# PAGE06_POWER_SWITCHES.net
KiCad netlist of a schematic drawn in Altium Designer
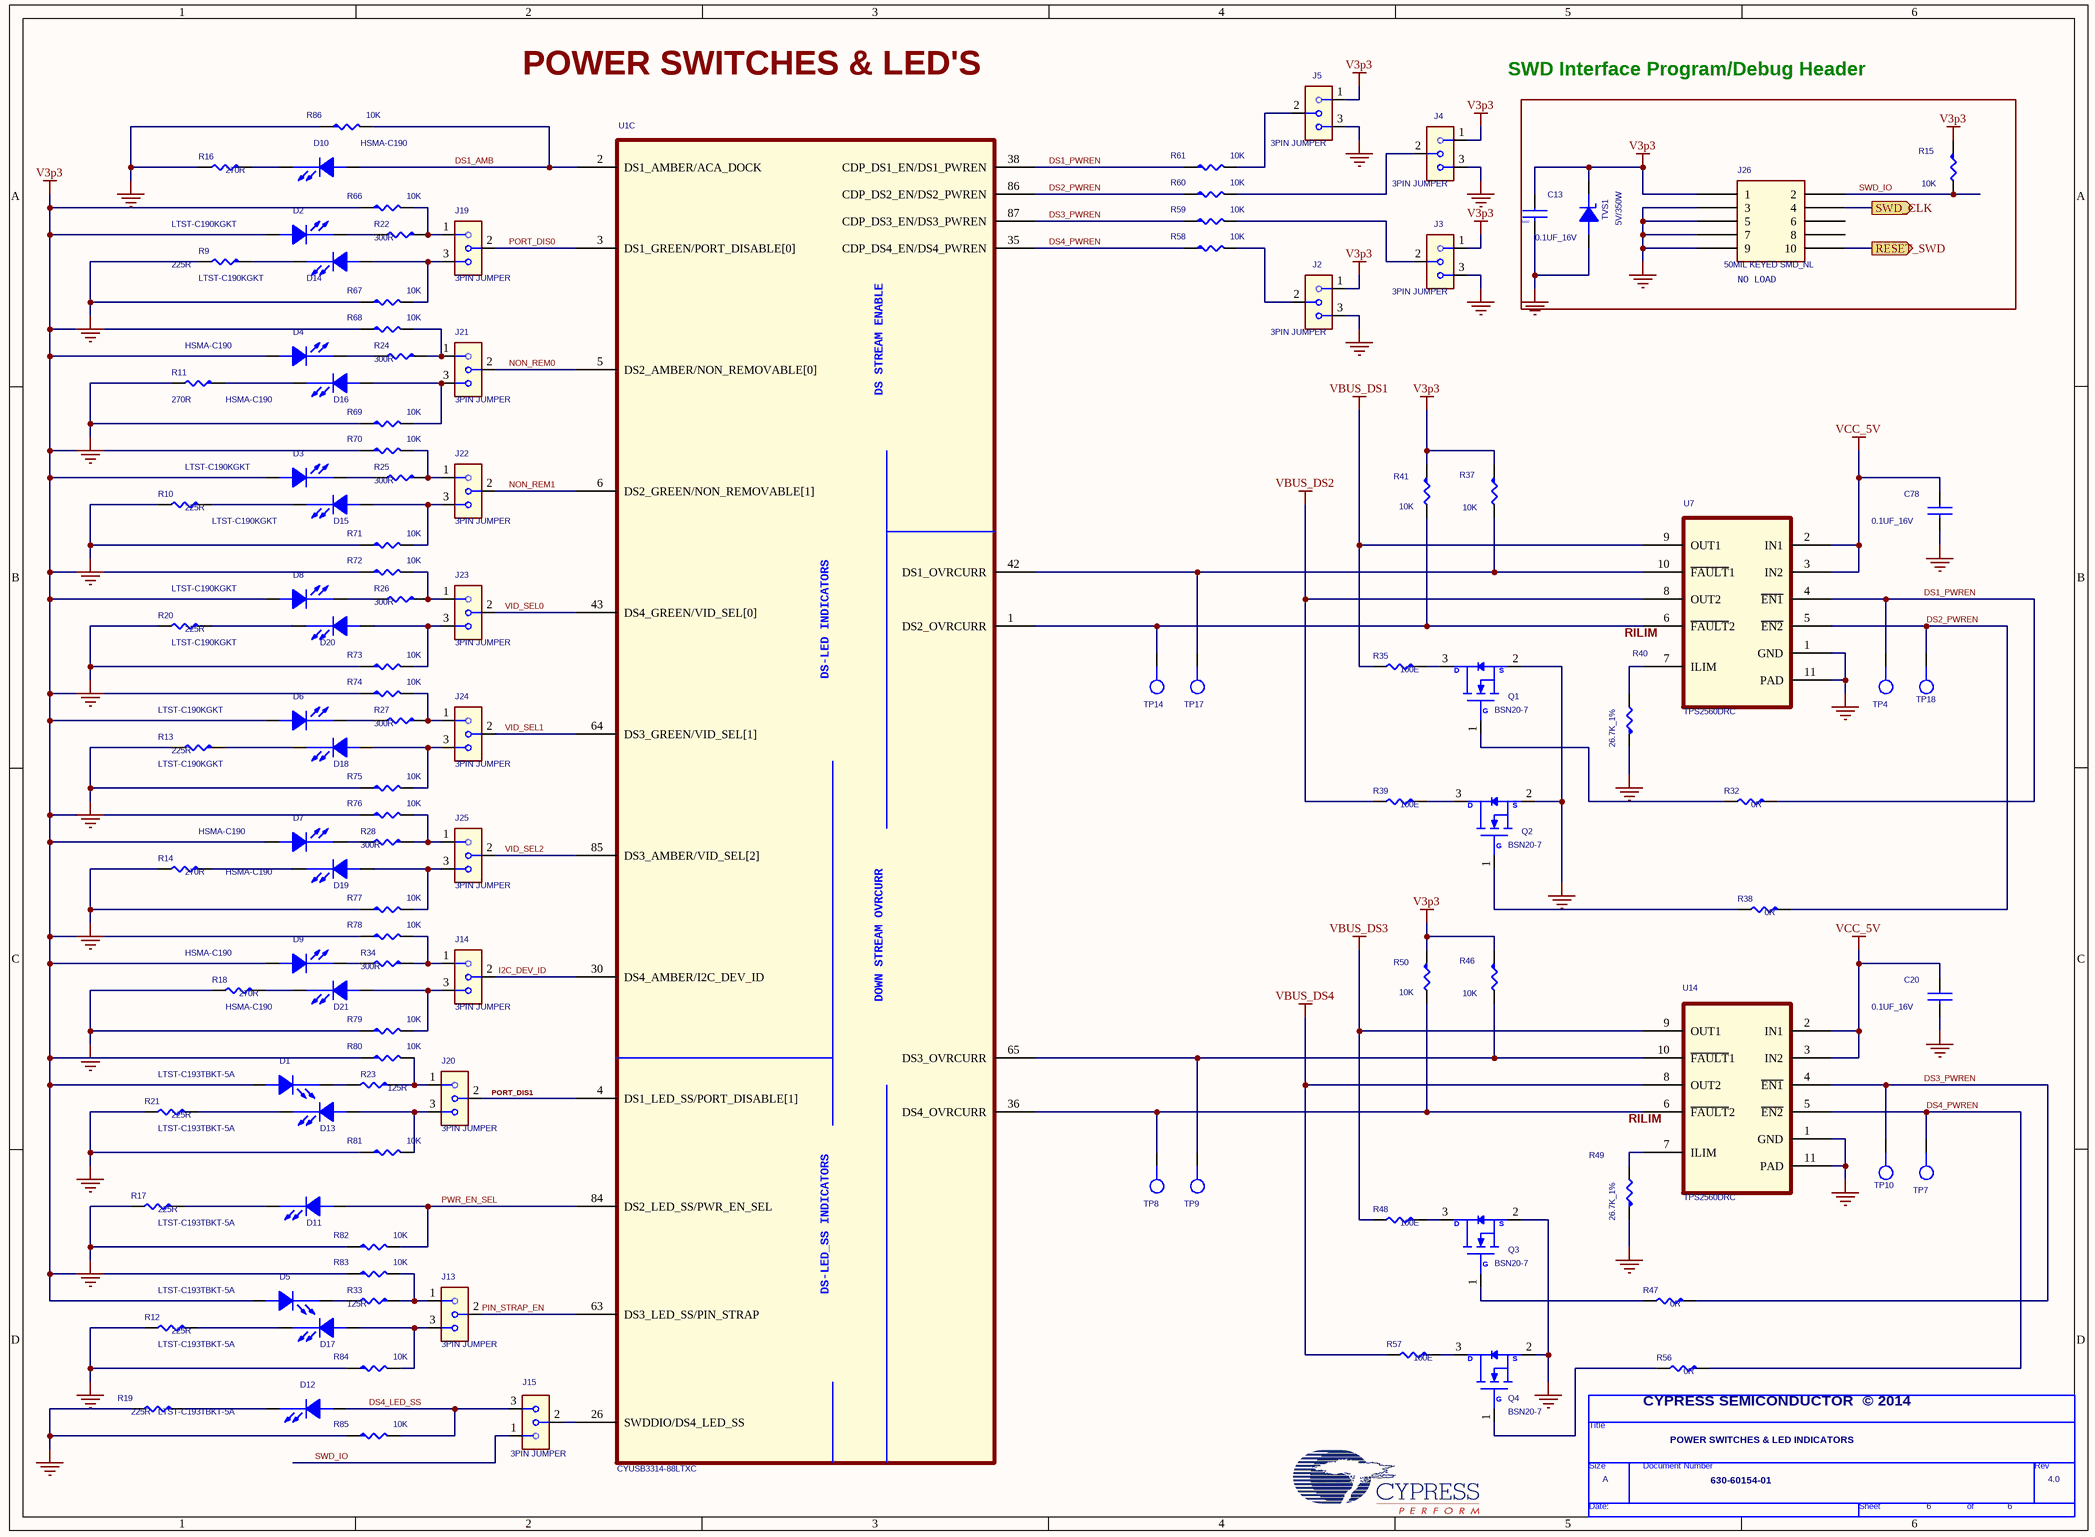
[diagram p0: PAGE06_POWER SWITCHES &.SchDoc]

(export (version "E")
  (design (tool "Eeschema 10.0.6"))
  (components
    (comp (ref "*")
      (value "TitleBlock0")
      (fields
        (field (name "PAGE COUNT") "6")
        (field (name "PAGE NUMBER") "6")
        (field (name "PAGE SIZE") "A")
        (field (name "TITLE") "POWER SWITCHES & LED INDICATORS")
        (field (name "REVCODE") "4.0")
        (field (name "DOC") "630-60154-01")
      )
      (libsource (lib "*") (part "TitleBlock0"))
    )
    (comp (ref "C13")
      (value "0.1UF_16V")
      (footprint "CAPC1005X55M")
      (description "CAP .1UF 16V CERAMIC Y5V 0402")
      (fields
        (field (name "CY_PART#") "730R-10010")
        (field (name "MANUFACTURER") "Panasonic - ECG")
        (field (name "CREATED BY") "SNF")
      )
      (libsource (lib "*") (part "0.1 uFd 0402"))
    )
    (comp (ref "C20")
      (value "0.1UF_16V")
      (footprint "CAPC1005X56M")
      (libsource (lib "*") (part "CAPACITOR NON-POL"))
    )
    (comp (ref "C78")
      (value "0.1UF_16V")
      (footprint "CAPC1005X56M")
      (libsource (lib "*") (part "CAPACITOR NON-POL"))
    )
    (comp (ref "D1") (value "LTST-C193TBKT-5A") (libsource (lib "*") (part "LED")))
    (comp (ref "D2") (value "LTST-C190KGKT") (libsource (lib "*") (part "LED")))
    (comp (ref "D3") (value "LTST-C190KGKT") (libsource (lib "*") (part "LED")))
    (comp (ref "D4") (value "HSMA-C190") (libsource (lib "*") (part "LED")))
    (comp (ref "D5") (value "LTST-C193TBKT-5A") (libsource (lib "*") (part "LED")))
    (comp (ref "D6") (value "LTST-C190KGKT") (libsource (lib "*") (part "LED")))
    (comp (ref "D7") (value "HSMA-C190") (libsource (lib "*") (part "LED")))
    (comp (ref "D8") (value "LTST-C190KGKT") (libsource (lib "*") (part "LED")))
    (comp (ref "D9") (value "HSMA-C190") (libsource (lib "*") (part "LED")))
    (comp (ref "D10") (value "HSMA-C190") (libsource (lib "*") (part "LED")))
    (comp (ref "D11") (value "LTST-C193TBKT-5A") (libsource (lib "*") (part "LED")))
    (comp (ref "D12") (value "LTST-C193TBKT-5A") (libsource (lib "*") (part "LED")))
    (comp (ref "D13") (value "LTST-C193TBKT-5A") (libsource (lib "*") (part "LED")))
    (comp (ref "D14") (value "LTST-C190KGKT") (libsource (lib "*") (part "LED")))
    (comp (ref "D15") (value "LTST-C190KGKT") (libsource (lib "*") (part "LED")))
    (comp (ref "D16") (value "HSMA-C190") (libsource (lib "*") (part "LED")))
    (comp (ref "D17") (value "LTST-C193TBKT-5A") (libsource (lib "*") (part "LED")))
    (comp (ref "D18") (value "LTST-C190KGKT") (libsource (lib "*") (part "LED")))
    (comp (ref "D19") (value "HSMA-C190") (libsource (lib "*") (part "LED")))
    (comp (ref "D20") (value "LTST-C190KGKT") (libsource (lib "*") (part "LED")))
    (comp (ref "D21") (value "HSMA-C190") (libsource (lib "*") (part "LED")))
    (comp (ref "J2")
      (value "3PIN JUMPER")
      (description "CONN HEADER VERT 3POS .100 TIN")
      (fields (field (name "MANUFACTURER") "Tyco Electronics") (field (name "PART NUMBER") "3-644456-3"))
      (libsource (lib "*") (part "3PIN JUM"))
    )
    (comp (ref "J3")
      (value "3PIN JUMPER")
      (description "CONN HEADER VERT 3POS .100 TIN")
      (fields (field (name "PART NUMBER") "3-644456-3") (field (name "MANUFACTURER") "Tyco Electronics"))
      (libsource (lib "*") (part "3PIN JUM"))
    )
    (comp (ref "J4")
      (value "3PIN JUMPER")
      (description "CONN HEADER VERT 3POS .100 TIN")
      (fields (field (name "MANUFACTURER") "Tyco Electronics") (field (name "PART NUMBER") "3-644456-3"))
      (libsource (lib "*") (part "3PIN JUM"))
    )
    (comp (ref "J5")
      (value "3PIN JUMPER")
      (description "CONN HEADER VERT 3POS .100 TIN")
      (fields (field (name "PART NUMBER") "3-644456-3") (field (name "MANUFACTURER") "Tyco Electronics"))
      (libsource (lib "*") (part "3PIN JUM"))
    )
    (comp (ref "J13")
      (value "3PIN JUMPER")
      (description "CONN HEADER VERT 3POS .100 TIN")
      (fields (field (name "PART NUMBER") "3-644456-3") (field (name "MANUFACTURER") "Tyco Electronics"))
      (libsource (lib "") (part "3PIN JUM_1"))
    )
    (comp (ref "J14")
      (value "3PIN JUMPER")
      (description "CONN HEADER VERT 3POS .100 TIN")
      (fields (field (name "MANUFACTURER") "Tyco Electronics") (field (name "PART NUMBER") "3-644456-3"))
      (libsource (lib "") (part "3PIN JUM_1"))
    )
    (comp (ref "J15")
      (value "3PIN JUMPER")
      (description "CONN HEADER VERT 3POS .100 TIN")
      (fields (field (name "PART NUMBER") "3-644456-3") (field (name "MANUFACTURER") "Tyco Electronics"))
      (libsource (lib "") (part "3PIN JUM_2"))
    )
    (comp (ref "J19")
      (value "3PIN JUMPER")
      (description "CONN HEADER VERT 3POS .100 TIN")
      (fields (field (name "PART NUMBER") "3-644456-3") (field (name "MANUFACTURER") "Tyco Electronics"))
      (libsource (lib "") (part "3PIN JUM_1"))
    )
    (comp (ref "J20")
      (value "3PIN JUMPER")
      (description "CONN HEADER VERT 3POS .100 TIN")
      (fields (field (name "PART NUMBER") "3-644456-3") (field (name "MANUFACTURER") "Tyco Electronics"))
      (libsource (lib "") (part "3PIN JUM_1"))
    )
    (comp (ref "J21")
      (value "3PIN JUMPER")
      (description "CONN HEADER VERT 3POS .100 TIN")
      (fields (field (name "PART NUMBER") "3-644456-3") (field (name "MANUFACTURER") "Tyco Electronics"))
      (libsource (lib "") (part "3PIN JUM_1"))
    )
    (comp (ref "J22")
      (value "3PIN JUMPER")
      (description "CONN HEADER VERT 3POS .100 TIN")
      (fields (field (name "PART NUMBER") "3-644456-3") (field (name "MANUFACTURER") "Tyco Electronics"))
      (libsource (lib "") (part "3PIN JUM_1"))
    )
    (comp (ref "J23")
      (value "3PIN JUMPER")
      (description "CONN HEADER VERT 3POS .100 TIN")
      (fields (field (name "MANUFACTURER") "Tyco Electronics") (field (name "PART NUMBER") "3-644456-3"))
      (libsource (lib "") (part "3PIN JUM_1"))
    )
    (comp (ref "J24")
      (value "3PIN JUMPER")
      (description "CONN HEADER VERT 3POS .100 TIN")
      (fields (field (name "PART NUMBER") "3-644456-3") (field (name "MANUFACTURER") "Tyco Electronics"))
      (libsource (lib "") (part "3PIN JUM_1"))
    )
    (comp (ref "J25")
      (value "3PIN JUMPER")
      (description "CONN HEADER VERT 3POS .100 TIN")
      (fields (field (name "MANUFACTURER") "Tyco Electronics") (field (name "PART NUMBER") "3-644456-3"))
      (libsource (lib "") (part "3PIN JUM_1"))
    )
    (comp (ref "J26")
      (value "50MIL KEYED SMD_NL")
      (footprint "SAMTEC_FTSH-105-01-L-DV-K")
      (description "CONN HEADER 10 PIN 50MIL KEYED SMD")
      (fields
        (field (name "PART NUMBER") "FTSH-105-01-L-DV-K")
        (field (name "MANUFACTURER") "Samtec")
        (field (name "LAST EDIT BY") "SNF")
      )
      (libsource (lib "*") (part "10 Pin Header 50mil Keyed SMD"))
    )
    (comp (ref "Q1")
      (value "BSN20-7")
      (description "MOSFET N-CH 50V 500MA SOT23")
      (fields (field (name "MANUFACTURER") "Diodes Inc"))
      (libsource (lib "*") (part "BSN20-7"))
    )
    (comp (ref "Q2")
      (value "BSN20-7")
      (description "MOSFET N-CH 50V 500MA SOT23")
      (fields (field (name "MANUFACTURER") "Diodes Inc"))
      (libsource (lib "*") (part "BSN20-7"))
    )
    (comp (ref "Q3")
      (value "BSN20-7")
      (description "MOSFET N-CH 50V 500MA SOT23")
      (fields (field (name "MANUFACTURER") "Diodes Inc"))
      (libsource (lib "*") (part "BSN20-7"))
    )
    (comp (ref "Q4")
      (value "BSN20-7")
      (description "MOSFET N-CH 50V 500MA SOT23")
      (fields (field (name "MANUFACTURER") "Diodes Inc"))
      (libsource (lib "*") (part "BSN20-7"))
    )
    (comp (ref "R9") (value "225R") (footprint "RESC1608X50M") (libsource (lib "*") (part "R_Dup1")))
    (comp (ref "R10") (value "225R") (footprint "RESC1608X50M") (libsource (lib "*") (part "R_Dup1")))
    (comp (ref "R11") (value "270R") (footprint "RESC1608X50M") (libsource (lib "*") (part "R_Dup1")))
    (comp (ref "R12") (value "225R") (footprint "RESC1608X50M") (libsource (lib "*") (part "R_Dup1")))
    (comp (ref "R13") (value "225R") (footprint "RESC1608X50M") (libsource (lib "*") (part "R_Dup1")))
    (comp (ref "R14") (value "270R") (footprint "RESC1608X50M") (libsource (lib "*") (part "R_Dup1")))
    (comp (ref "R15")
      (value "10K")
      (footprint "RESC1005X40M")
      (description "RES 10.0K OHM 1/10W 1% 0603 SMD")
      (fields (field (name "MANUFACTURER") "Panasonic - ECG") (field (name "PART NUMBER") "ERJ-3EKF1002V"))
      (libsource (lib "*") (part "R_Dup1"))
    )
    (comp (ref "R16") (value "270R") (footprint "RESC1608X50M") (libsource (lib "*") (part "R_Dup1")))
    (comp (ref "R17") (value "225R") (footprint "RESC1608X50M") (libsource (lib "*") (part "R_Dup1")))
    (comp (ref "R18") (value "270R") (footprint "RESC1608X50M") (libsource (lib "*") (part "R_Dup1")))
    (comp (ref "R19") (value "225R") (footprint "RESC1608X50M") (libsource (lib "*") (part "R_Dup1")))
    (comp (ref "R20") (value "225R") (footprint "RESC1608X50M") (libsource (lib "*") (part "R_Dup1")))
    (comp (ref "R21") (value "225R") (footprint "RESC1608X50M") (libsource (lib "*") (part "R_Dup1")))
    (comp (ref "R22") (value "300R") (footprint "RESC2012X65M") (libsource (lib "*") (part "R_Dup1")))
    (comp (ref "R23") (value "125R") (footprint "RESC2012X65M") (libsource (lib "*") (part "R_Dup1")))
    (comp (ref "R24") (value "300R") (footprint "RESC2012X65M") (libsource (lib "*") (part "R_Dup1")))
    (comp (ref "R25") (value "300R") (footprint "RESC2012X65M") (libsource (lib "*") (part "R_Dup1")))
    (comp (ref "R26") (value "300R") (footprint "RESC2012X65M") (libsource (lib "*") (part "R_Dup1")))
    (comp (ref "R27") (value "300R") (footprint "RESC2012X65M") (libsource (lib "*") (part "R_Dup1")))
    (comp (ref "R28") (value "300R") (footprint "RESC2012X65M") (libsource (lib "*") (part "R_Dup1")))
    (comp (ref "R32") (value "0R") (footprint "RESC1608X50M") (libsource (lib "*") (part "R_Dup1")))
    (comp (ref "R33") (value "125R") (footprint "RESC2012X65M") (libsource (lib "*") (part "R_Dup1")))
    (comp (ref "R34") (value "300R") (footprint "RESC2012X65M") (libsource (lib "*") (part "R_Dup1")))
    (comp (ref "R35") (value "100E") (footprint "RESC1608X50M") (libsource (lib "*") (part "R_Dup1")))
    (comp (ref "R37")
      (value "10K")
      (footprint "RESC1005X40M")
      (description "RES 10.0K OHM 1/10W 1% 0603 SMD")
      (fields (field (name "MANUFACTURER") "Panasonic - ECG") (field (name "PART NUMBER") "ERJ-3EKF1002V"))
      (libsource (lib "*") (part "R_Dup1"))
    )
    (comp (ref "R38") (value "0R") (footprint "RESC1608X50M") (libsource (lib "*") (part "R_Dup1")))
    (comp (ref "R39") (value "100E") (footprint "RESC1608X50M") (libsource (lib "*") (part "R_Dup1")))
    (comp (ref "R40")
      (value "26.7K_1%")
      (footprint "RESC1005X40M")
      (description "RES 28.0K OHM 1/10W 1% 0402 SMD")
      (fields (field (name "MANUFACTURER") "Panasonic") (field (name "PART NUMBER") "ERJ-2RKF2802X"))
      (libsource (lib "*") (part "R_Dup1"))
    )
    (comp (ref "R41")
      (value "10K")
      (footprint "RESC1005X40M")
      (description "RES 10.0K OHM 1/10W 1% 0603 SMD")
      (fields (field (name "PART NUMBER") "ERJ-3EKF1002V") (field (name "MANUFACTURER") "Panasonic - ECG"))
      (libsource (lib "*") (part "R_Dup1"))
    )
    (comp (ref "R46")
      (value "10K")
      (footprint "RESC1005X40M")
      (description "RES 10.0K OHM 1/10W 1% 0603 SMD")
      (fields (field (name "PART NUMBER") "ERJ-3EKF1002V") (field (name "MANUFACTURER") "Panasonic - ECG"))
      (libsource (lib "*") (part "R_Dup1"))
    )
    (comp (ref "R47") (value "0R") (footprint "RESC1608X50M") (libsource (lib "*") (part "R_Dup1")))
    (comp (ref "R48") (value "100E") (footprint "RESC1608X50M") (libsource (lib "*") (part "R_Dup1")))
    (comp (ref "R49")
      (value "26.7K_1%")
      (footprint "RESC1005X40M")
      (description "RES 28.0K OHM 1/10W 1% 0402 SMD")
      (fields (field (name "TOLERANCE") "1%") (field (name "PART NUMBER") "ERJ-2RKF2802X"))
      (libsource (lib "*") (part "R_Dup1"))
    )
    (comp (ref "R50")
      (value "10K")
      (footprint "RESC1005X40M")
      (description "RES 10.0K OHM 1/10W 1% 0603 SMD")
      (fields (field (name "MANUFACTURER") "Panasonic - ECG") (field (name "PART NUMBER") "ERJ-3EKF1002V"))
      (libsource (lib "*") (part "R_Dup1"))
    )
    (comp (ref "R56") (value "0R") (footprint "RESC1608X50M") (libsource (lib "*") (part "R_Dup1")))
    (comp (ref "R57") (value "100E") (footprint "RESC1608X50M") (libsource (lib "*") (part "R_Dup1")))
    (comp (ref "R58")
      (value "10K")
      (footprint "RESC1005X40M")
      (description "RES 10.0K OHM 1/10W 1% 0603 SMD")
      (fields (field (name "MANUFACTURER") "Panasonic - ECG") (field (name "PART NUMBER") "ERJ-3EKF1002V"))
      (libsource (lib "*") (part "R_Dup1"))
    )
    (comp (ref "R59")
      (value "10K")
      (footprint "RESC1005X40M")
      (description "RES 10.0K OHM 1/10W 1% 0603 SMD")
      (fields (field (name "MANUFACTURER") "Panasonic - ECG") (field (name "PART NUMBER") "ERJ-3EKF1002V"))
      (libsource (lib "*") (part "R_Dup1"))
    )
    (comp (ref "R60")
      (value "10K")
      (footprint "RESC1005X40M")
      (description "RES 10.0K OHM 1/10W 1% 0603 SMD")
      (fields (field (name "MANUFACTURER") "Panasonic - ECG") (field (name "PART NUMBER") "ERJ-3EKF1002V"))
      (libsource (lib "*") (part "R_Dup1"))
    )
    (comp (ref "R61")
      (value "10K")
      (footprint "RESC1005X40M")
      (description "RES 10.0K OHM 1/10W 1% 0603 SMD")
      (fields (field (name "MANUFACTURER") "Panasonic - ECG") (field (name "PART NUMBER") "ERJ-3EKF1002V"))
      (libsource (lib "*") (part "R_Dup1"))
    )
    (comp (ref "R66")
      (value "10K")
      (footprint "RESC1005X40M")
      (description "RES 10.0K OHM 1/10W 1% 0603 SMD")
      (fields (field (name "MANUFACTURER") "Panasonic - ECG") (field (name "PART NUMBER") "ERJ-3EKF1002V"))
      (libsource (lib "*") (part "R_Dup1"))
    )
    (comp (ref "R67")
      (value "10K")
      (footprint "RESC1005X40M")
      (description "RES 10.0K OHM 1/10W 1% 0603 SMD")
      (fields (field (name "MANUFACTURER") "Panasonic - ECG") (field (name "PART NUMBER") "ERJ-3EKF1002V"))
      (libsource (lib "*") (part "R_Dup1"))
    )
    (comp (ref "R68")
      (value "10K")
      (footprint "RESC1005X40M")
      (description "RES 10.0K OHM 1/10W 1% 0603 SMD")
      (fields (field (name "PART NUMBER") "ERJ-3EKF1002V") (field (name "MANUFACTURER") "Panasonic - ECG"))
      (libsource (lib "*") (part "R_Dup1"))
    )
    (comp (ref "R69")
      (value "10K")
      (footprint "RESC1005X40M")
      (description "RES 10.0K OHM 1/10W 1% 0603 SMD")
      (fields (field (name "PART NUMBER") "ERJ-3EKF1002V") (field (name "MANUFACTURER") "Panasonic - ECG"))
      (libsource (lib "*") (part "R_Dup1"))
    )
    (comp (ref "R70")
      (value "10K")
      (footprint "RESC1005X40M")
      (description "RES 10.0K OHM 1/10W 1% 0603 SMD")
      (fields (field (name "MANUFACTURER") "Panasonic - ECG") (field (name "PART NUMBER") "ERJ-3EKF1002V"))
      (libsource (lib "*") (part "R_Dup1"))
    )
    (comp (ref "R71")
      (value "10K")
      (footprint "RESC1005X40M")
      (description "RES 10.0K OHM 1/10W 1% 0603 SMD")
      (fields (field (name "MANUFACTURER") "Panasonic - ECG") (field (name "PART NUMBER") "ERJ-3EKF1002V"))
      (libsource (lib "*") (part "R_Dup1"))
    )
    (comp (ref "R72")
      (value "10K")
      (footprint "RESC1005X40M")
      (description "RES 10.0K OHM 1/10W 1% 0603 SMD")
      (fields (field (name "PART NUMBER") "ERJ-3EKF1002V") (field (name "MANUFACTURER") "Panasonic - ECG"))
      (libsource (lib "*") (part "R_Dup1"))
    )
    (comp (ref "R73")
      (value "10K")
      (footprint "RESC1005X40M")
      (description "RES 10.0K OHM 1/10W 1% 0603 SMD")
      (fields (field (name "MANUFACTURER") "Panasonic - ECG") (field (name "PART NUMBER") "ERJ-3EKF1002V"))
      (libsource (lib "*") (part "R_Dup1"))
    )
    (comp (ref "R74")
      (value "10K")
      (footprint "RESC1005X40M")
      (description "RES 10.0K OHM 1/10W 1% 0603 SMD")
      (fields (field (name "MANUFACTURER") "Panasonic - ECG") (field (name "PART NUMBER") "ERJ-3EKF1002V"))
      (libsource (lib "*") (part "R_Dup1"))
    )
    (comp (ref "R75")
      (value "10K")
      (footprint "RESC1005X40M")
      (description "RES 10.0K OHM 1/10W 1% 0603 SMD")
      (fields (field (name "MANUFACTURER") "Panasonic - ECG") (field (name "PART NUMBER") "ERJ-3EKF1002V"))
      (libsource (lib "*") (part "R_Dup1"))
    )
    (comp (ref "R76")
      (value "10K")
      (footprint "RESC1005X40M")
      (description "RES 10.0K OHM 1/10W 1% 0603 SMD")
      (fields (field (name "MANUFACTURER") "Panasonic - ECG") (field (name "PART NUMBER") "ERJ-3EKF1002V"))
      (libsource (lib "*") (part "R_Dup1"))
    )
    (comp (ref "R77")
      (value "10K")
      (footprint "RESC1005X40M")
      (description "RES 10.0K OHM 1/10W 1% 0603 SMD")
      (fields (field (name "MANUFACTURER") "Panasonic - ECG") (field (name "PART NUMBER") "ERJ-3EKF1002V"))
      (libsource (lib "*") (part "R_Dup1"))
    )
    (comp (ref "R78")
      (value "10K")
      (footprint "RESC1005X40M")
      (description "RES 10.0K OHM 1/10W 1% 0603 SMD")
      (fields (field (name "PART NUMBER") "ERJ-3EKF1002V") (field (name "MANUFACTURER") "Panasonic - ECG"))
      (libsource (lib "*") (part "R_Dup1"))
    )
    (comp (ref "R79")
      (value "10K")
      (footprint "RESC1005X40M")
      (description "RES 10.0K OHM 1/10W 1% 0603 SMD")
      (fields (field (name "MANUFACTURER") "Panasonic - ECG") (field (name "PART NUMBER") "ERJ-3EKF1002V"))
      (libsource (lib "*") (part "R_Dup1"))
    )
    (comp (ref "R80")
      (value "10K")
      (footprint "RESC1005X40M")
      (description "RES 10.0K OHM 1/10W 1% 0603 SMD")
      (fields (field (name "MANUFACTURER") "Panasonic - ECG") (field (name "PART NUMBER") "ERJ-3EKF1002V"))
      (libsource (lib "*") (part "R_Dup1"))
    )
    (comp (ref "R81")
      (value "10K")
      (footprint "RESC1005X40M")
      (description "RES 10.0K OHM 1/10W 1% 0603 SMD")
      (fields (field (name "PART NUMBER") "ERJ-3EKF1002V") (field (name "MANUFACTURER") "Panasonic - ECG"))
      (libsource (lib "*") (part "R_Dup1"))
    )
    (comp (ref "R82")
      (value "10K")
      (footprint "RESC1005X40M")
      (description "RES 10.0K OHM 1/10W 1% 0603 SMD")
      (fields (field (name "MANUFACTURER") "Panasonic - ECG") (field (name "PART NUMBER") "ERJ-3EKF1002V"))
      (libsource (lib "*") (part "R_Dup1"))
    )
    (comp (ref "R83")
      (value "10K")
      (footprint "RESC1005X40M")
      (description "RES 10.0K OHM 1/10W 1% 0603 SMD")
      (fields (field (name "MANUFACTURER") "Panasonic - ECG") (field (name "PART NUMBER") "ERJ-3EKF1002V"))
      (libsource (lib "*") (part "R_Dup1"))
    )
    (comp (ref "R84")
      (value "10K")
      (footprint "RESC1005X40M")
      (description "RES 10.0K OHM 1/10W 1% 0603 SMD")
      (fields (field (name "MANUFACTURER") "Panasonic - ECG") (field (name "PART NUMBER") "ERJ-3EKF1002V"))
      (libsource (lib "*") (part "R_Dup1"))
    )
    (comp (ref "R85")
      (value "10K")
      (footprint "RESC1005X40M")
      (description "RES 10.0K OHM 1/10W 1% 0603 SMD")
      (fields (field (name "MANUFACTURER") "Panasonic - ECG") (field (name "PART NUMBER") "ERJ-3EKF1002V"))
      (libsource (lib "*") (part "R_Dup1"))
    )
    (comp (ref "R86")
      (value "10K")
      (footprint "RESC1005X40M")
      (description "RES 10.0K OHM 1/10W 1% 0603 SMD")
      (fields (field (name "MANUFACTURER") "Panasonic - ECG") (field (name "PART NUMBER") "ERJ-3EKF1002V"))
      (libsource (lib "*") (part "R_Dup1"))
    )
    (comp (ref "TP4") (value "TEST POINT") (footprint "TP25C50") (libsource (lib "*") (part "TP")))
    (comp (ref "TP7") (value "TEST POINT") (footprint "TP25C50") (libsource (lib "*") (part "TP")))
    (comp (ref "TP8") (value "TEST POINT") (footprint "TP25C50") (libsource (lib "*") (part "TP")))
    (comp (ref "TP9")
      (value "TP_YEL")
      (footprint "KEYSTONE_5000")
      (description "TEST POINT PC MINI .040\"D RED")
      (fields (field (name "PART NUMBER") "5000") (field (name "MANUFACTURER") "Keystone"))
      (libsource (lib "*") (part "TP"))
    )
    (comp (ref "TP10")
      (value "TP_YEL")
      (footprint "KEYSTONE_5000")
      (description "TEST POINT PC MINI .040\"D RED")
      (fields (field (name "MANUFACTURER") "Keystone") (field (name "PART NUMBER") "5000"))
      (libsource (lib "*") (part "TP"))
    )
    (comp (ref "TP14") (value "TEST POINT") (footprint "TP25C50") (libsource (lib "*") (part "TP")))
    (comp (ref "TP17")
      (value "TP_YEL")
      (footprint "KEYSTONE_5000")
      (description "TEST POINT PC MINI .040\"D RED")
      (fields (field (name "PART NUMBER") "5000") (field (name "MANUFACTURER") "Keystone"))
      (libsource (lib "*") (part "TP"))
    )
    (comp (ref "TP18")
      (value "TP_YEL")
      (footprint "KEYSTONE_5000")
      (description "TEST POINT PC MINI .040\"D RED")
      (fields (field (name "MANUFACTURER") "Keystone") (field (name "PART NUMBER") "5000"))
      (libsource (lib "*") (part "TP"))
    )
    (comp (ref "TVS1")
      (value "5V/350W")
      (footprint "SOD2513X120M")
      (description "TVS UNIDIR 350W 5V SOD-323")
      (fields
        (field (name "PART NUMBER") "SD05.TCT")
        (field (name "MANUFACTURER") "Dioded Inc.")
        (field (name "LASTEDITBY") "gir")
      )
      (libsource (lib "*") (part "TVS 5V SOD-323_0"))
    )
    (comp (ref "U1")
      (value "CYUSB3314-88LTXC")
      (footprint "QFN40P1000X1000X100-89M")
      (libsource (lib "*") (part "CYUSB3314-88LTXC_2"))
    )
    (comp (ref "U7")
      (value "TPS2560DRC")
      (footprint "SON50P300X300X100-11M")
      (libsource (lib "*") (part "TPS2560DRC"))
    )
    (comp (ref "U14")
      (value "TPS2560DRC")
      (footprint "SON50P300X300X100-11M")
      (libsource (lib "*") (part "TPS2560DRC"))
    )
  )
  (nets
    (net (code "1") (name "/DS1_AMB") (class "Default")
      (node (ref "D10") (pin "1") (pinfunction "ANODE_1") (pintype "passive"))
      (node (ref "R86") (pin "2") (pinfunction "2_2") (pintype "passive"))
      (node (ref "U1") (pin "2") (pinfunction "DS1_AMBER/ACA_DOCK_2") (pintype "passive"))
    )
    (net (code "2") (name "/DS1_PWREN") (class "Default")
      (node (ref "R32") (pin "1") (pinfunction "1_1") (pintype "passive"))
      (node (ref "R61") (pin "1") (pinfunction "1_1") (pintype "passive"))
      (node (ref "TP4") (pin "1") (pinfunction "TP_1") (pintype "passive"))
      (node (ref "U1") (pin "38") (pinfunction "CDP_DS1_EN/DS1_PWREN_38") (pintype "passive"))
      (node (ref "U7") (pin "4") (pinfunction "~{EN1}_4") (pintype "passive"))
    )
    (net (code "3") (name "/DS2_PWREN") (class "Default")
      (node (ref "R38") (pin "1") (pinfunction "1_1") (pintype "passive"))
      (node (ref "R60") (pin "1") (pinfunction "1_1") (pintype "passive"))
      (node (ref "TP18") (pin "1") (pinfunction "TP_1") (pintype "passive"))
      (node (ref "U1") (pin "86") (pinfunction "CDP_DS2_EN/DS2_PWREN_86") (pintype "passive"))
      (node (ref "U7") (pin "5") (pinfunction "~{EN2}_5") (pintype "passive"))
    )
    (net (code "4") (name "/DS3_PWREN") (class "Default")
      (node (ref "R47") (pin "1") (pinfunction "1_1") (pintype "passive"))
      (node (ref "R59") (pin "1") (pinfunction "1_1") (pintype "passive"))
      (node (ref "TP10") (pin "1") (pinfunction "TP_1") (pintype "passive"))
      (node (ref "U1") (pin "87") (pinfunction "CDP_DS3_EN/DS3_PWREN_87") (pintype "passive"))
      (node (ref "U14") (pin "4") (pinfunction "~{EN1}_4") (pintype "passive"))
    )
    (net (code "5") (name "/DS4_LED_SS") (class "Default")
      (node (ref "D12") (pin "1") (pinfunction "ANODE_1") (pintype "passive"))
      (node (ref "J15") (pin "3") (pinfunction "3_3") (pintype "passive"))
      (node (ref "R85") (pin "2") (pinfunction "2_2") (pintype "passive"))
    )
    (net (code "6") (name "/DS4_PWREN") (class "Default")
      (node (ref "R56") (pin "1") (pinfunction "1_1") (pintype "passive"))
      (node (ref "R58") (pin "1") (pinfunction "1_1") (pintype "passive"))
      (node (ref "TP7") (pin "1") (pinfunction "TP_1") (pintype "passive"))
      (node (ref "U1") (pin "35") (pinfunction "CDP_DS4_EN/DS4_PWREN_35") (pintype "passive"))
      (node (ref "U14") (pin "5") (pinfunction "~{EN2}_5") (pintype "passive"))
    )
    (net (code "7") (name "/I2C_DEV_ID") (class "Default")
      (node (ref "J14") (pin "2") (pinfunction "2_2") (pintype "passive"))
      (node (ref "U1") (pin "30") (pinfunction "DS4_AMBER/I2C_DEV_ID_30") (pintype "passive"))
    )
    (net (code "8") (name "/NON_REM0") (class "Default")
      (node (ref "J21") (pin "2") (pinfunction "2_2") (pintype "passive"))
      (node (ref "U1") (pin "5") (pinfunction "DS2_AMBER/NON_REMOVABLE[0]_5") (pintype "passive"))
    )
    (net (code "9") (name "/NON_REM1") (class "Default")
      (node (ref "J22") (pin "2") (pinfunction "2_2") (pintype "passive"))
      (node (ref "U1") (pin "6") (pinfunction "DS2_GREEN/NON_REMOVABLE[1]_6") (pintype "passive"))
    )
    (net (code "10") (name "/PIN_STRAP_EN") (class "Default")
      (node (ref "J13") (pin "2") (pinfunction "2_2") (pintype "passive"))
      (node (ref "U1") (pin "63") (pinfunction "DS3_LED_SS/PIN_STRAP_63") (pintype "passive"))
    )
    (net (code "11") (name "/PORT_DIS0") (class "Default")
      (node (ref "J19") (pin "2") (pinfunction "2_2") (pintype "passive"))
      (node (ref "U1") (pin "3") (pinfunction "DS1_GREEN/PORT_DISABLE[0]_3") (pintype "passive"))
    )
    (net (code "12") (name "/PORT_DIS1") (class "Default")
      (node (ref "J20") (pin "2") (pinfunction "2_2") (pintype "passive"))
      (node (ref "U1") (pin "4") (pinfunction "DS1_LED_SS/PORT_DISABLE[1]_4") (pintype "passive"))
    )
    (net (code "13") (name "/PWR_EN_SEL") (class "Default")
      (node (ref "D11") (pin "1") (pinfunction "ANODE_1") (pintype "passive"))
      (node (ref "R82") (pin "2") (pinfunction "2_2") (pintype "passive"))
      (node (ref "U1") (pin "84") (pinfunction "DS2_LED_SS/PWR_EN_SEL_84") (pintype "passive"))
    )
    (net (code "14") (name "/RESET_SWD") (class "Default")
      (node (ref "J26") (pin "10") (pinfunction "10_10") (pintype "passive"))
    )
    (net (code "15") (name "/SWD_CLK") (class "Default")
      (node (ref "J26") (pin "4") (pinfunction "4_4") (pintype "passive"))
    )
    (net (code "16") (name "/SWD_IO") (class "Default")
      (node (ref "J15") (pin "1") (pinfunction "1_1") (pintype "passive"))
      (node (ref "J26") (pin "2") (pinfunction "2_2") (pintype "passive"))
      (node (ref "R15") (pin "2") (pinfunction "2_2") (pintype "passive"))
    )
    (net (code "17") (name "/VID_SEL0") (class "Default")
      (node (ref "J23") (pin "2") (pinfunction "2_2") (pintype "passive"))
      (node (ref "U1") (pin "43") (pinfunction "DS4_GREEN/VID_SEL[0]_43") (pintype "passive"))
    )
    (net (code "18") (name "/VID_SEL1") (class "Default")
      (node (ref "J24") (pin "2") (pinfunction "2_2") (pintype "passive"))
      (node (ref "U1") (pin "64") (pinfunction "DS3_GREEN/VID_SEL[1]_64") (pintype "passive"))
    )
    (net (code "19") (name "/VID_SEL2") (class "Default")
      (node (ref "J25") (pin "2") (pinfunction "2_2") (pintype "passive"))
      (node (ref "U1") (pin "85") (pinfunction "DS3_AMBER/VID_SEL[2]_85") (pintype "passive"))
    )
    (net (code "20") (name "GND") (class "Default")
      (node (ref "C13") (pin "2") (pinfunction "2_2") (pintype "passive"))
      (node (ref "C20") (pin "2") (pinfunction "2_2") (pintype "passive"))
      (node (ref "C78") (pin "2") (pinfunction "2_2") (pintype "passive"))
      (node (ref "J2") (pin "3") (pinfunction "3_3") (pintype "passive"))
      (node (ref "J26") (pin "3") (pinfunction "3_3") (pintype "passive"))
      (node (ref "J26") (pin "5") (pinfunction "5_5") (pintype "passive"))
      (node (ref "J26") (pin "7") (pinfunction "7_7") (pintype "passive"))
      (node (ref "J26") (pin "9") (pinfunction "9_9") (pintype "passive"))
      (node (ref "J3") (pin "3") (pinfunction "3_3") (pintype "passive"))
      (node (ref "J4") (pin "3") (pinfunction "3_3") (pintype "passive"))
      (node (ref "J5") (pin "3") (pinfunction "3_3") (pintype "passive"))
      (node (ref "Q1") (pin "2") (pinfunction "S_2") (pintype "passive"))
      (node (ref "Q2") (pin "2") (pinfunction "S_2") (pintype "passive"))
      (node (ref "Q3") (pin "2") (pinfunction "S_2") (pintype "passive"))
      (node (ref "Q4") (pin "2") (pinfunction "S_2") (pintype "passive"))
      (node (ref "R10") (pin "2") (pinfunction "2_2") (pintype "passive"))
      (node (ref "R11") (pin "2") (pinfunction "2_2") (pintype "passive"))
      (node (ref "R12") (pin "2") (pinfunction "2_2") (pintype "passive"))
      (node (ref "R13") (pin "2") (pinfunction "2_2") (pintype "passive"))
      (node (ref "R14") (pin "2") (pinfunction "2_2") (pintype "passive"))
      (node (ref "R16") (pin "2") (pinfunction "2_2") (pintype "passive"))
      (node (ref "R17") (pin "2") (pinfunction "2_2") (pintype "passive"))
      (node (ref "R18") (pin "2") (pinfunction "2_2") (pintype "passive"))
      (node (ref "R19") (pin "2") (pinfunction "2_2") (pintype "passive"))
      (node (ref "R20") (pin "2") (pinfunction "2_2") (pintype "passive"))
      (node (ref "R21") (pin "2") (pinfunction "2_2") (pintype "passive"))
      (node (ref "R40") (pin "1") (pinfunction "1_1") (pintype "passive"))
      (node (ref "R49") (pin "1") (pinfunction "1_1") (pintype "passive"))
      (node (ref "R67") (pin "1") (pinfunction "1_1") (pintype "passive"))
      (node (ref "R69") (pin "1") (pinfunction "1_1") (pintype "passive"))
      (node (ref "R71") (pin "1") (pinfunction "1_1") (pintype "passive"))
      (node (ref "R73") (pin "1") (pinfunction "1_1") (pintype "passive"))
      (node (ref "R75") (pin "1") (pinfunction "1_1") (pintype "passive"))
      (node (ref "R77") (pin "1") (pinfunction "1_1") (pintype "passive"))
      (node (ref "R79") (pin "1") (pinfunction "1_1") (pintype "passive"))
      (node (ref "R81") (pin "1") (pinfunction "1_1") (pintype "passive"))
      (node (ref "R82") (pin "1") (pinfunction "1_1") (pintype "passive"))
      (node (ref "R84") (pin "1") (pinfunction "1_1") (pintype "passive"))
      (node (ref "R85") (pin "1") (pinfunction "1_1") (pintype "passive"))
      (node (ref "R86") (pin "1") (pinfunction "1_1") (pintype "passive"))
      (node (ref "R9") (pin "2") (pinfunction "2_2") (pintype "passive"))
      (node (ref "TVS1") (pin "2") (pinfunction "A_2") (pintype "passive"))
      (node (ref "U14") (pin "1") (pinfunction "GND_1") (pintype "passive"))
      (node (ref "U14") (pin "11") (pinfunction "PAD_11") (pintype "passive"))
      (node (ref "U7") (pin "1") (pinfunction "GND_1") (pintype "passive"))
      (node (ref "U7") (pin "11") (pinfunction "PAD_11") (pintype "passive"))
    )
    (net (code "21") (name "Net-(D1-CATHODE)") (class "Default")
      (node (ref "D1") (pin "2") (pinfunction "CATHODE_2") (pintype "passive"))
      (node (ref "R23") (pin "2") (pinfunction "2_2") (pintype "passive"))
    )
    (net (code "22") (name "Net-(D2-CATHODE)") (class "Default")
      (node (ref "D2") (pin "2") (pinfunction "CATHODE_2") (pintype "passive"))
      (node (ref "R22") (pin "2") (pinfunction "2_2") (pintype "passive"))
    )
    (net (code "23") (name "Net-(D3-CATHODE)") (class "Default")
      (node (ref "D3") (pin "2") (pinfunction "CATHODE_2") (pintype "passive"))
      (node (ref "R25") (pin "2") (pinfunction "2_2") (pintype "passive"))
    )
    (net (code "24") (name "Net-(D4-CATHODE)") (class "Default")
      (node (ref "D4") (pin "2") (pinfunction "CATHODE_2") (pintype "passive"))
      (node (ref "R24") (pin "2") (pinfunction "2_2") (pintype "passive"))
    )
    (net (code "25") (name "Net-(D5-CATHODE)") (class "Default")
      (node (ref "D5") (pin "2") (pinfunction "CATHODE_2") (pintype "passive"))
      (node (ref "R33") (pin "2") (pinfunction "2_2") (pintype "passive"))
    )
    (net (code "26") (name "Net-(D6-CATHODE)") (class "Default")
      (node (ref "D6") (pin "2") (pinfunction "CATHODE_2") (pintype "passive"))
      (node (ref "R27") (pin "2") (pinfunction "2_2") (pintype "passive"))
    )
    (net (code "27") (name "Net-(D7-CATHODE)") (class "Default")
      (node (ref "D7") (pin "2") (pinfunction "CATHODE_2") (pintype "passive"))
      (node (ref "R28") (pin "2") (pinfunction "2_2") (pintype "passive"))
    )
    (net (code "28") (name "Net-(D8-CATHODE)") (class "Default")
      (node (ref "D8") (pin "2") (pinfunction "CATHODE_2") (pintype "passive"))
      (node (ref "R26") (pin "2") (pinfunction "2_2") (pintype "passive"))
    )
    (net (code "29") (name "Net-(D9-CATHODE)") (class "Default")
      (node (ref "D9") (pin "2") (pinfunction "CATHODE_2") (pintype "passive"))
      (node (ref "R34") (pin "2") (pinfunction "2_2") (pintype "passive"))
    )
    (net (code "30") (name "Net-(D10-CATHODE)") (class "Default")
      (node (ref "D10") (pin "2") (pinfunction "CATHODE_2") (pintype "passive"))
      (node (ref "R16") (pin "1") (pinfunction "1_1") (pintype "passive"))
    )
    (net (code "31") (name "Net-(D11-CATHODE)") (class "Default")
      (node (ref "D11") (pin "2") (pinfunction "CATHODE_2") (pintype "passive"))
      (node (ref "R17") (pin "1") (pinfunction "1_1") (pintype "passive"))
    )
    (net (code "32") (name "Net-(D12-CATHODE)") (class "Default")
      (node (ref "D12") (pin "2") (pinfunction "CATHODE_2") (pintype "passive"))
      (node (ref "R19") (pin "1") (pinfunction "1_1") (pintype "passive"))
    )
    (net (code "33") (name "Net-(D13-ANODE)") (class "Default")
      (node (ref "D13") (pin "1") (pinfunction "ANODE_1") (pintype "passive"))
      (node (ref "J20") (pin "3") (pinfunction "3_3") (pintype "passive"))
      (node (ref "R81") (pin "2") (pinfunction "2_2") (pintype "passive"))
    )
    (net (code "34") (name "Net-(D13-CATHODE)") (class "Default")
      (node (ref "D13") (pin "2") (pinfunction "CATHODE_2") (pintype "passive"))
      (node (ref "R21") (pin "1") (pinfunction "1_1") (pintype "passive"))
    )
    (net (code "35") (name "Net-(D14-ANODE)") (class "Default")
      (node (ref "D14") (pin "1") (pinfunction "ANODE_1") (pintype "passive"))
      (node (ref "J19") (pin "3") (pinfunction "3_3") (pintype "passive"))
      (node (ref "R67") (pin "2") (pinfunction "2_2") (pintype "passive"))
    )
    (net (code "36") (name "Net-(D14-CATHODE)") (class "Default")
      (node (ref "D14") (pin "2") (pinfunction "CATHODE_2") (pintype "passive"))
      (node (ref "R9") (pin "1") (pinfunction "1_1") (pintype "passive"))
    )
    (net (code "37") (name "Net-(D15-ANODE)") (class "Default")
      (node (ref "D15") (pin "1") (pinfunction "ANODE_1") (pintype "passive"))
      (node (ref "J22") (pin "3") (pinfunction "3_3") (pintype "passive"))
      (node (ref "R71") (pin "2") (pinfunction "2_2") (pintype "passive"))
    )
    (net (code "38") (name "Net-(D15-CATHODE)") (class "Default")
      (node (ref "D15") (pin "2") (pinfunction "CATHODE_2") (pintype "passive"))
      (node (ref "R10") (pin "1") (pinfunction "1_1") (pintype "passive"))
    )
    (net (code "39") (name "Net-(D16-ANODE)") (class "Default")
      (node (ref "D16") (pin "1") (pinfunction "ANODE_1") (pintype "passive"))
      (node (ref "J21") (pin "3") (pinfunction "3_3") (pintype "passive"))
      (node (ref "R69") (pin "2") (pinfunction "2_2") (pintype "passive"))
    )
    (net (code "40") (name "Net-(D16-CATHODE)") (class "Default")
      (node (ref "D16") (pin "2") (pinfunction "CATHODE_2") (pintype "passive"))
      (node (ref "R11") (pin "1") (pinfunction "1_1") (pintype "passive"))
    )
    (net (code "41") (name "Net-(D17-ANODE)") (class "Default")
      (node (ref "D17") (pin "1") (pinfunction "ANODE_1") (pintype "passive"))
      (node (ref "J13") (pin "3") (pinfunction "3_3") (pintype "passive"))
      (node (ref "R84") (pin "2") (pinfunction "2_2") (pintype "passive"))
    )
    (net (code "42") (name "Net-(D17-CATHODE)") (class "Default")
      (node (ref "D17") (pin "2") (pinfunction "CATHODE_2") (pintype "passive"))
      (node (ref "R12") (pin "1") (pinfunction "1_1") (pintype "passive"))
    )
    (net (code "43") (name "Net-(D18-ANODE)") (class "Default")
      (node (ref "D18") (pin "1") (pinfunction "ANODE_1") (pintype "passive"))
      (node (ref "J24") (pin "3") (pinfunction "3_3") (pintype "passive"))
      (node (ref "R75") (pin "2") (pinfunction "2_2") (pintype "passive"))
    )
    (net (code "44") (name "Net-(D18-CATHODE)") (class "Default")
      (node (ref "D18") (pin "2") (pinfunction "CATHODE_2") (pintype "passive"))
      (node (ref "R13") (pin "1") (pinfunction "1_1") (pintype "passive"))
    )
    (net (code "45") (name "Net-(D19-ANODE)") (class "Default")
      (node (ref "D19") (pin "1") (pinfunction "ANODE_1") (pintype "passive"))
      (node (ref "J25") (pin "3") (pinfunction "3_3") (pintype "passive"))
      (node (ref "R77") (pin "2") (pinfunction "2_2") (pintype "passive"))
    )
    (net (code "46") (name "Net-(D19-CATHODE)") (class "Default")
      (node (ref "D19") (pin "2") (pinfunction "CATHODE_2") (pintype "passive"))
      (node (ref "R14") (pin "1") (pinfunction "1_1") (pintype "passive"))
    )
    (net (code "47") (name "Net-(D20-ANODE)") (class "Default")
      (node (ref "D20") (pin "1") (pinfunction "ANODE_1") (pintype "passive"))
      (node (ref "J23") (pin "3") (pinfunction "3_3") (pintype "passive"))
      (node (ref "R73") (pin "2") (pinfunction "2_2") (pintype "passive"))
    )
    (net (code "48") (name "Net-(D20-CATHODE)") (class "Default")
      (node (ref "D20") (pin "2") (pinfunction "CATHODE_2") (pintype "passive"))
      (node (ref "R20") (pin "1") (pinfunction "1_1") (pintype "passive"))
    )
    (net (code "49") (name "Net-(D21-ANODE)") (class "Default")
      (node (ref "D21") (pin "1") (pinfunction "ANODE_1") (pintype "passive"))
      (node (ref "J14") (pin "3") (pinfunction "3_3") (pintype "passive"))
      (node (ref "R79") (pin "2") (pinfunction "2_2") (pintype "passive"))
    )
    (net (code "50") (name "Net-(D21-CATHODE)") (class "Default")
      (node (ref "D21") (pin "2") (pinfunction "CATHODE_2") (pintype "passive"))
      (node (ref "R18") (pin "1") (pinfunction "1_1") (pintype "passive"))
    )
    (net (code "51") (name "Net-(J2-Pad2)") (class "Default")
      (node (ref "J2") (pin "2") (pinfunction "2_2") (pintype "passive"))
      (node (ref "R58") (pin "2") (pinfunction "2_2") (pintype "passive"))
    )
    (net (code "52") (name "Net-(J3-Pad2)") (class "Default")
      (node (ref "J3") (pin "2") (pinfunction "2_2") (pintype "passive"))
      (node (ref "R59") (pin "2") (pinfunction "2_2") (pintype "passive"))
    )
    (net (code "53") (name "Net-(J4-Pad2)") (class "Default")
      (node (ref "J4") (pin "2") (pinfunction "2_2") (pintype "passive"))
      (node (ref "R60") (pin "2") (pinfunction "2_2") (pintype "passive"))
    )
    (net (code "54") (name "Net-(J5-Pad2)") (class "Default")
      (node (ref "J5") (pin "2") (pinfunction "2_2") (pintype "passive"))
      (node (ref "R61") (pin "2") (pinfunction "2_2") (pintype "passive"))
    )
    (net (code "55") (name "Net-(J13-Pad1)") (class "Default")
      (node (ref "J13") (pin "1") (pinfunction "1_1") (pintype "passive"))
      (node (ref "R33") (pin "1") (pinfunction "1_1") (pintype "passive"))
      (node (ref "R83") (pin "2") (pinfunction "2_2") (pintype "passive"))
    )
    (net (code "56") (name "Net-(J14-Pad1)") (class "Default")
      (node (ref "J14") (pin "1") (pinfunction "1_1") (pintype "passive"))
      (node (ref "R34") (pin "1") (pinfunction "1_1") (pintype "passive"))
      (node (ref "R78") (pin "2") (pinfunction "2_2") (pintype "passive"))
    )
    (net (code "57") (name "Net-(J19-Pad1)") (class "Default")
      (node (ref "J19") (pin "1") (pinfunction "1_1") (pintype "passive"))
      (node (ref "R22") (pin "1") (pinfunction "1_1") (pintype "passive"))
      (node (ref "R66") (pin "2") (pinfunction "2_2") (pintype "passive"))
    )
    (net (code "58") (name "Net-(J20-Pad1)") (class "Default")
      (node (ref "J20") (pin "1") (pinfunction "1_1") (pintype "passive"))
      (node (ref "R23") (pin "1") (pinfunction "1_1") (pintype "passive"))
      (node (ref "R80") (pin "2") (pinfunction "2_2") (pintype "passive"))
    )
    (net (code "59") (name "Net-(J21-Pad1)") (class "Default")
      (node (ref "J21") (pin "1") (pinfunction "1_1") (pintype "passive"))
      (node (ref "R24") (pin "1") (pinfunction "1_1") (pintype "passive"))
      (node (ref "R68") (pin "2") (pinfunction "2_2") (pintype "passive"))
    )
    (net (code "60") (name "Net-(J22-Pad1)") (class "Default")
      (node (ref "J22") (pin "1") (pinfunction "1_1") (pintype "passive"))
      (node (ref "R25") (pin "1") (pinfunction "1_1") (pintype "passive"))
      (node (ref "R70") (pin "2") (pinfunction "2_2") (pintype "passive"))
    )
    (net (code "61") (name "Net-(J23-Pad1)") (class "Default")
      (node (ref "J23") (pin "1") (pinfunction "1_1") (pintype "passive"))
      (node (ref "R26") (pin "1") (pinfunction "1_1") (pintype "passive"))
      (node (ref "R72") (pin "2") (pinfunction "2_2") (pintype "passive"))
    )
    (net (code "62") (name "Net-(J24-Pad1)") (class "Default")
      (node (ref "J24") (pin "1") (pinfunction "1_1") (pintype "passive"))
      (node (ref "R27") (pin "1") (pinfunction "1_1") (pintype "passive"))
      (node (ref "R74") (pin "2") (pinfunction "2_2") (pintype "passive"))
    )
    (net (code "63") (name "Net-(J25-Pad1)") (class "Default")
      (node (ref "J25") (pin "1") (pinfunction "1_1") (pintype "passive"))
      (node (ref "R28") (pin "1") (pinfunction "1_1") (pintype "passive"))
      (node (ref "R76") (pin "2") (pinfunction "2_2") (pintype "passive"))
    )
    (net (code "64") (name "Net-(Q1-D)") (class "Default")
      (node (ref "Q1") (pin "3") (pinfunction "D_3") (pintype "passive"))
      (node (ref "R35") (pin "1") (pinfunction "1_1") (pintype "passive"))
    )
    (net (code "65") (name "Net-(Q1-G)") (class "Default")
      (node (ref "Q1") (pin "1") (pinfunction "G_1") (pintype "passive"))
      (node (ref "R32") (pin "2") (pinfunction "2_2") (pintype "passive"))
    )
    (net (code "66") (name "Net-(Q2-D)") (class "Default")
      (node (ref "Q2") (pin "3") (pinfunction "D_3") (pintype "passive"))
      (node (ref "R39") (pin "1") (pinfunction "1_1") (pintype "passive"))
    )
    (net (code "67") (name "Net-(Q2-G)") (class "Default")
      (node (ref "Q2") (pin "1") (pinfunction "G_1") (pintype "passive"))
      (node (ref "R38") (pin "2") (pinfunction "2_2") (pintype "passive"))
    )
    (net (code "68") (name "Net-(Q3-D)") (class "Default")
      (node (ref "Q3") (pin "3") (pinfunction "D_3") (pintype "passive"))
      (node (ref "R48") (pin "1") (pinfunction "1_1") (pintype "passive"))
    )
    (net (code "69") (name "Net-(Q3-G)") (class "Default")
      (node (ref "Q3") (pin "1") (pinfunction "G_1") (pintype "passive"))
      (node (ref "R47") (pin "2") (pinfunction "2_2") (pintype "passive"))
    )
    (net (code "70") (name "Net-(Q4-D)") (class "Default")
      (node (ref "Q4") (pin "3") (pinfunction "D_3") (pintype "passive"))
      (node (ref "R57") (pin "1") (pinfunction "1_1") (pintype "passive"))
    )
    (net (code "71") (name "Net-(Q4-G)") (class "Default")
      (node (ref "Q4") (pin "1") (pinfunction "G_1") (pintype "passive"))
      (node (ref "R56") (pin "2") (pinfunction "2_2") (pintype "passive"))
    )
    (net (code "72") (name "Net-(TP8-TP)") (class "Default")
      (node (ref "R50") (pin "2") (pinfunction "2_2") (pintype "passive"))
      (node (ref "TP8") (pin "1") (pinfunction "TP_1") (pintype "passive"))
      (node (ref "U1") (pin "36") (pinfunction "DS4_OVRCURR_36") (pintype "passive"))
      (node (ref "U14") (pin "6") (pinfunction "~{FAULT}2_6") (pintype "passive"))
    )
    (net (code "73") (name "Net-(TP9-TP)") (class "Default")
      (node (ref "R46") (pin "2") (pinfunction "2_2") (pintype "passive"))
      (node (ref "TP9") (pin "1") (pinfunction "TP_1") (pintype "passive"))
      (node (ref "U1") (pin "65") (pinfunction "DS3_OVRCURR_65") (pintype "passive"))
      (node (ref "U14") (pin "10") (pinfunction "~{FAULT}1_10") (pintype "passive"))
    )
    (net (code "74") (name "Net-(TP14-TP)") (class "Default")
      (node (ref "R41") (pin "2") (pinfunction "2_2") (pintype "passive"))
      (node (ref "TP14") (pin "1") (pinfunction "TP_1") (pintype "passive"))
      (node (ref "U1") (pin "1") (pinfunction "DS2_OVRCURR_1") (pintype "passive"))
      (node (ref "U7") (pin "6") (pinfunction "~{FAULT}2_6") (pintype "passive"))
    )
    (net (code "75") (name "Net-(TP17-TP)") (class "Default")
      (node (ref "R37") (pin "2") (pinfunction "2_2") (pintype "passive"))
      (node (ref "TP17") (pin "1") (pinfunction "TP_1") (pintype "passive"))
      (node (ref "U1") (pin "42") (pinfunction "DS1_OVRCURR_42") (pintype "passive"))
      (node (ref "U7") (pin "10") (pinfunction "~{FAULT}1_10") (pintype "passive"))
    )
    (net (code "76") (name "Net-(U1C-SWDDIO{slash}DS4_LED_SS)") (class "Default")
      (node (ref "J15") (pin "2") (pinfunction "2_2") (pintype "passive"))
      (node (ref "U1") (pin "26") (pinfunction "SWDDIO/DS4_LED_SS_26") (pintype "passive"))
    )
    (net (code "77") (name "Net-(U7-ILIM)") (class "Default")
      (node (ref "R40") (pin "2") (pinfunction "2_2") (pintype "passive"))
      (node (ref "U7") (pin "7") (pinfunction "ILIM_7") (pintype "passive"))
    )
    (net (code "78") (name "Net-(U14-ILIM)") (class "Default")
      (node (ref "R49") (pin "2") (pinfunction "2_2") (pintype "passive"))
      (node (ref "U14") (pin "7") (pinfunction "ILIM_7") (pintype "passive"))
    )
    (net (code "79") (name "V3p3") (class "Default")
      (node (ref "C13") (pin "1") (pinfunction "1_1") (pintype "passive"))
      (node (ref "D1") (pin "1") (pinfunction "ANODE_1") (pintype "passive"))
      (node (ref "D2") (pin "1") (pinfunction "ANODE_1") (pintype "passive"))
      (node (ref "D3") (pin "1") (pinfunction "ANODE_1") (pintype "passive"))
      (node (ref "D4") (pin "1") (pinfunction "ANODE_1") (pintype "passive"))
      (node (ref "D5") (pin "1") (pinfunction "ANODE_1") (pintype "passive"))
      (node (ref "D6") (pin "1") (pinfunction "ANODE_1") (pintype "passive"))
      (node (ref "D7") (pin "1") (pinfunction "ANODE_1") (pintype "passive"))
      (node (ref "D8") (pin "1") (pinfunction "ANODE_1") (pintype "passive"))
      (node (ref "D9") (pin "1") (pinfunction "ANODE_1") (pintype "passive"))
      (node (ref "J2") (pin "1") (pinfunction "1_1") (pintype "passive"))
      (node (ref "J26") (pin "1") (pinfunction "1_1") (pintype "passive"))
      (node (ref "J3") (pin "1") (pinfunction "1_1") (pintype "passive"))
      (node (ref "J4") (pin "1") (pinfunction "1_1") (pintype "passive"))
      (node (ref "J5") (pin "1") (pinfunction "1_1") (pintype "passive"))
      (node (ref "R15") (pin "1") (pinfunction "1_1") (pintype "passive"))
      (node (ref "R37") (pin "1") (pinfunction "1_1") (pintype "passive"))
      (node (ref "R41") (pin "1") (pinfunction "1_1") (pintype "passive"))
      (node (ref "R46") (pin "1") (pinfunction "1_1") (pintype "passive"))
      (node (ref "R50") (pin "1") (pinfunction "1_1") (pintype "passive"))
      (node (ref "R66") (pin "1") (pinfunction "1_1") (pintype "passive"))
      (node (ref "R68") (pin "1") (pinfunction "1_1") (pintype "passive"))
      (node (ref "R70") (pin "1") (pinfunction "1_1") (pintype "passive"))
      (node (ref "R72") (pin "1") (pinfunction "1_1") (pintype "passive"))
      (node (ref "R74") (pin "1") (pinfunction "1_1") (pintype "passive"))
      (node (ref "R76") (pin "1") (pinfunction "1_1") (pintype "passive"))
      (node (ref "R78") (pin "1") (pinfunction "1_1") (pintype "passive"))
      (node (ref "R80") (pin "1") (pinfunction "1_1") (pintype "passive"))
      (node (ref "R83") (pin "1") (pinfunction "1_1") (pintype "passive"))
      (node (ref "TVS1") (pin "1") (pinfunction "K_1") (pintype "passive"))
    )
    (net (code "80") (name "VBUS_DS1") (class "Default")
      (node (ref "R35") (pin "2") (pinfunction "2_2") (pintype "passive"))
      (node (ref "U7") (pin "9") (pinfunction "OUT1_9") (pintype "passive"))
    )
    (net (code "81") (name "VBUS_DS2") (class "Default")
      (node (ref "R39") (pin "2") (pinfunction "2_2") (pintype "passive"))
      (node (ref "U7") (pin "8") (pinfunction "OUT2_8") (pintype "passive"))
    )
    (net (code "82") (name "VBUS_DS3") (class "Default")
      (node (ref "R48") (pin "2") (pinfunction "2_2") (pintype "passive"))
      (node (ref "U14") (pin "9") (pinfunction "OUT1_9") (pintype "passive"))
    )
    (net (code "83") (name "VBUS_DS4") (class "Default")
      (node (ref "R57") (pin "2") (pinfunction "2_2") (pintype "passive"))
      (node (ref "U14") (pin "8") (pinfunction "OUT2_8") (pintype "passive"))
    )
    (net (code "84") (name "VCC_5V") (class "Default")
      (node (ref "C20") (pin "1") (pinfunction "1_1") (pintype "passive"))
      (node (ref "C78") (pin "1") (pinfunction "1_1") (pintype "passive"))
      (node (ref "U14") (pin "2") (pinfunction "IN1_2") (pintype "passive"))
      (node (ref "U14") (pin "3") (pinfunction "IN2_3") (pintype "passive"))
      (node (ref "U7") (pin "2") (pinfunction "IN1_2") (pintype "passive"))
      (node (ref "U7") (pin "3") (pinfunction "IN2_3") (pintype "passive"))
    )
    (net (code "85") (name "unconnected-(J26-Pad6)") (class "Default")
      (node (ref "J26") (pin "6") (pinfunction "6_6") (pintype "passive"))
    )
    (net (code "86") (name "unconnected-(J26-Pad8)") (class "Default")
      (node (ref "J26") (pin "8") (pinfunction "8_8") (pintype "passive"))
    )
  )
)
